# ethernet_1gbe_ext_magn.net
KiCad netlist of a schematic drawn in Altium Designer
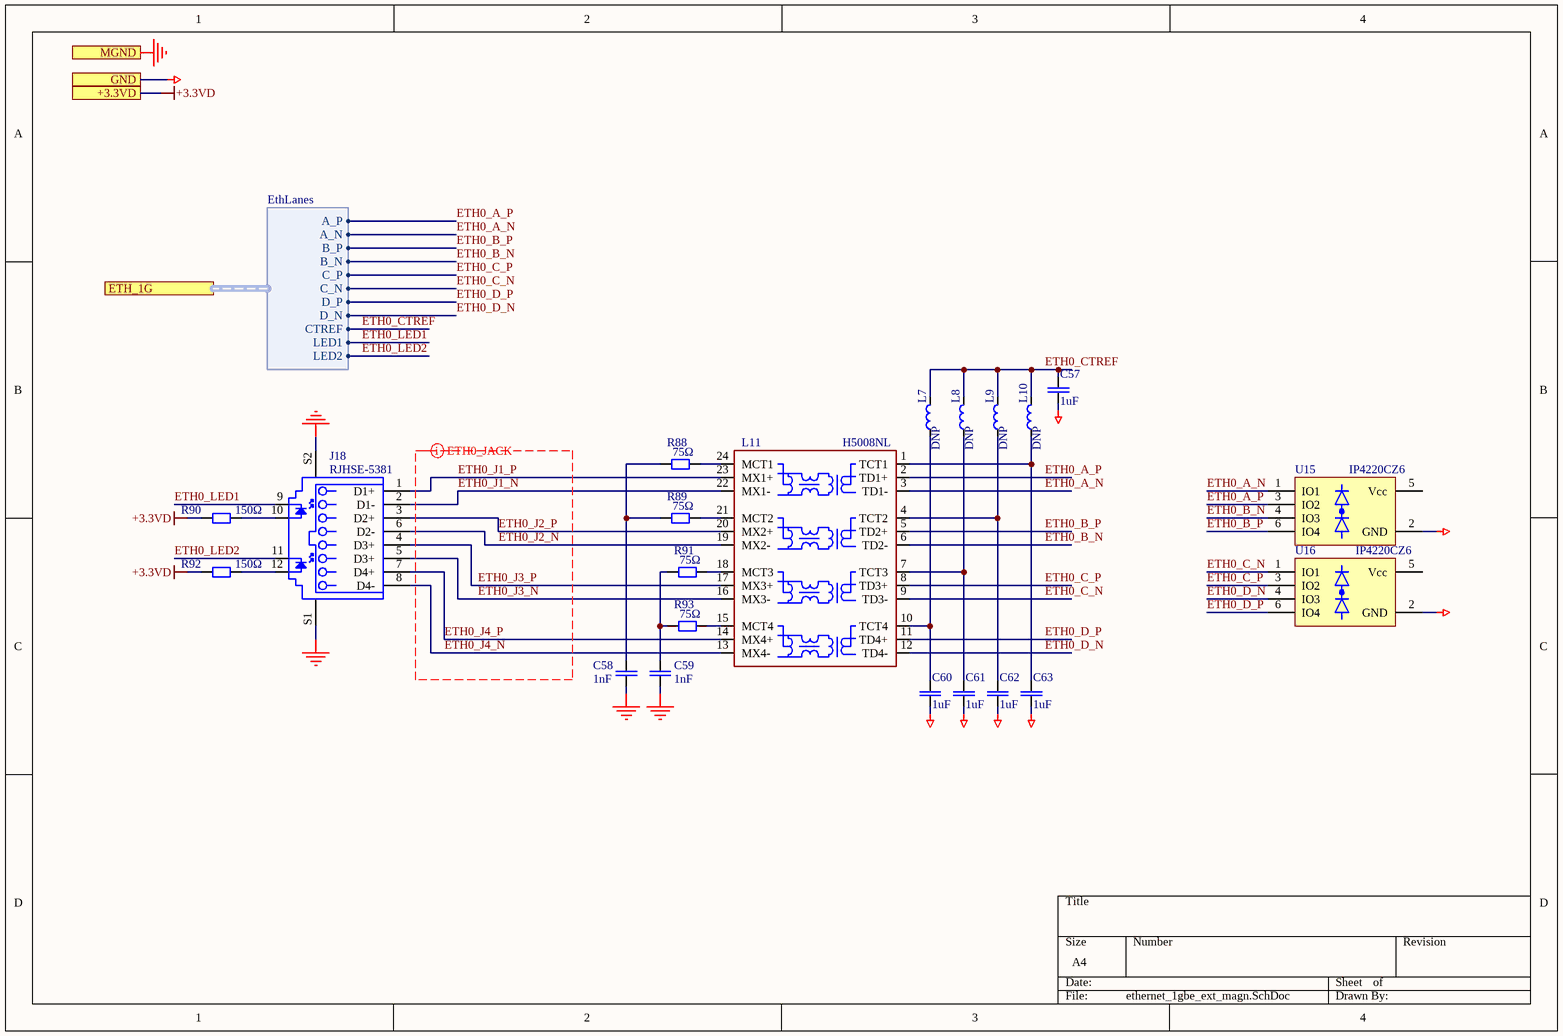
[diagram p0: ethernet_1gbe_ext_magn.SchDoc]

(export (version "E")
  (design (tool "Eeschema 10.0.6"))
  (components
    (comp (ref "C57")
      (value "1uF")
      (footprint "CAPC2012N")
      (description "Generic ceramic SMD capacitor")
      (fields (field (name "MAINTAINER") "Evgeniy Kotov"))
      (libsource (lib "[Capacitors] Capacitors SMD") (part "CAPC"))
    )
    (comp (ref "C58")
      (value "1nF")
      (footprint "CAPC3216N")
      (description "Generic ceramic SMD capacitor\r\n+' x '+Voltage Rating")
      (fields (field (name "Comment") "1nF; 2kV") (field (name "MAINTAINER") "Evgeniy Kotov"))
      (libsource (lib "[Capacitors] Capacitors SMD") (part "CAPC"))
    )
    (comp (ref "C59")
      (value "1nF")
      (footprint "CAPC3216N")
      (description "Generic ceramic SMD capacitor")
      (fields (field (name "Comment") "1nF; 2kV") (field (name "MAINTAINER") "Evgeniy Kotov"))
      (libsource (lib "[Capacitors] Capacitors SMD") (part "CAPC"))
    )
    (comp (ref "C60")
      (value "1uF")
      (footprint "CAPC2012N")
      (description "Generic ceramic SMD capacitor")
      (fields (field (name "MAINTAINER") "Evgeniy Kotov"))
      (libsource (lib "[Capacitors] Capacitors SMD") (part "CAPC"))
    )
    (comp (ref "C61")
      (value "1uF")
      (footprint "CAPC2012N")
      (description "Generic ceramic SMD capacitor")
      (fields (field (name "MAINTAINER") "Evgeniy Kotov"))
      (libsource (lib "[Capacitors] Capacitors SMD") (part "CAPC"))
    )
    (comp (ref "C62")
      (value "1uF")
      (footprint "CAPC2012N")
      (description "Generic ceramic SMD capacitor")
      (fields (field (name "MAINTAINER") "Evgeniy Kotov"))
      (libsource (lib "[Capacitors] Capacitors SMD") (part "CAPC"))
    )
    (comp (ref "C63")
      (value "1uF")
      (footprint "CAPC2012N")
      (description "Generic ceramic SMD capacitor")
      (fields (field (name "MAINTAINER") "Evgeniy Kotov"))
      (libsource (lib "[Capacitors] Capacitors SMD") (part "CAPC"))
    )
    (comp (ref "J18")
      (value "RJHSE-5381")
      (footprint "AMPH-RJHSE-5381_V")
      (fields (field (name "MANUFACTURER") "Amphenol"))
      (libsource (lib "[Connectors] Miscellaneous") (part "RJ45-RJHSE-5381"))
    )
    (comp (ref "L7")
      (value "DNP")
      (footprint "INDC2012N")
      (description "Ferrite Beads, 0805, 1 kOhm")
      (fields (field (name "TOLERANCE") "25%") (field (name "MAINTAINER") "Evgeniy Kotov"))
      (libsource (lib "[Inductors & Transformers] Inductors SMD") (part "BLM21RK102SN1D"))
    )
    (comp (ref "L8")
      (value "DNP")
      (footprint "INDC2012N")
      (description "Ferrite Beads, 0805, 1 kOhm")
      (fields (field (name "TOLERANCE") "25%") (field (name "MAINTAINER") "Evgeniy Kotov"))
      (libsource (lib "[Inductors & Transformers] Inductors SMD") (part "BLM21RK102SN1D"))
    )
    (comp (ref "L9")
      (value "DNP")
      (footprint "INDC2012N")
      (description "Ferrite Beads, 0805, 1 kOhm")
      (fields (field (name "TOLERANCE") "25%") (field (name "MAINTAINER") "Evgeniy Kotov"))
      (libsource (lib "[Inductors & Transformers] Inductors SMD") (part "BLM21RK102SN1D"))
    )
    (comp (ref "L10")
      (value "DNP")
      (footprint "INDC2012N")
      (description "Ferrite Beads, 0805, 1 kOhm")
      (fields (field (name "TOLERANCE") "25%") (field (name "MAINTAINER") "Evgeniy Kotov"))
      (libsource (lib "[Inductors & Transformers] Inductors SMD") (part "BLM21RK102SN1D"))
    )
    (comp (ref "L11")
      (value "H5008NL")
      (footprint "SMD_HX508")
      (description "LAN Transformer fog 1GbE, 12 coils, 4 pairs.")
      (fields (field (name "TOLERANCE") "2%") (field (name "MAINTAINER") "Evgeniy Kotov"))
      (libsource (lib "[Inductors & Transformers] Inductors SMD") (part "LAN_1G_TR_H5008NL"))
    )
    (comp (ref "R88")
      (value "75Ω")
      (footprint "RESC2012N")
      (description "Resistor, Generic, SMD")
      (fields (field (name "MAINTAINER") "Evgeniy Kotov"))
      (libsource (lib "[Resistors] Resistors SMD") (part "RESC"))
    )
    (comp (ref "R89")
      (value "75Ω")
      (footprint "RESC2012N")
      (description "Resistor, Generic, SMD")
      (fields (field (name "MAINTAINER") "Evgeniy Kotov"))
      (libsource (lib "[Resistors] Resistors SMD") (part "RESC"))
    )
    (comp (ref "R90")
      (value "150Ω")
      (footprint "RESC2012N")
      (description "Resistor, Generic, SMD")
      (fields (field (name "MAINTAINER") "Evgeniy Kotov"))
      (libsource (lib "[Resistors] Resistors SMD") (part "RESC"))
    )
    (comp (ref "R91")
      (value "75Ω")
      (footprint "RESC2012N")
      (description "Resistor, Generic, SMD")
      (fields (field (name "MAINTAINER") "Evgeniy Kotov"))
      (libsource (lib "[Resistors] Resistors SMD") (part "RESC"))
    )
    (comp (ref "R92")
      (value "150Ω")
      (footprint "RESC2012N")
      (description "Resistor, Generic, SMD")
      (fields (field (name "MAINTAINER") "Evgeniy Kotov"))
      (libsource (lib "[Resistors] Resistors SMD") (part "RESC"))
    )
    (comp (ref "R93")
      (value "75Ω")
      (footprint "RESC2012N")
      (description "Resistor, Generic, SMD")
      (fields (field (name "MAINTAINER") "Evgeniy Kotov"))
      (libsource (lib "[Resistors] Resistors SMD") (part "RESC"))
    )
    (comp (ref "U15")
      (value "IP4220CZ6")
      (footprint "SOT95P285X110-6N")
      (description "Transimpedance Amplifier; Selectable-Feedback Resistance")
      (fields (field (name "MAINTAINER") "Evgeniy Kotov"))
      (libsource (lib "[ICs And Semiconductors] Diodes") (part "IP4220CZ6"))
    )
    (comp (ref "U16")
      (value "IP4220CZ6")
      (footprint "SOT95P285X110-6N")
      (description "Transimpedance Amplifier; Selectable-Feedback Resistance")
      (fields (field (name "MAINTAINER") "Evgeniy Kotov"))
      (libsource (lib "[ICs And Semiconductors] Diodes") (part "IP4220CZ6"))
    )
  )
  (nets
    (net (code "2") (name "+3.3VD") (class "Default")
      (node (ref "R90") (pin "1") (pintype "passive"))
      (node (ref "R92") (pin "1") (pintype "passive"))
    )
    (net (code "3") (name "/ETH0_A_N") (class "Default")
      (node (ref "L11") (pin "3") (pinfunction "TD1-_3") (pintype "passive"))
      (node (ref "U15") (pin "1") (pinfunction "IO1_1") (pintype "passive"))
    )
    (net (code "4") (name "/ETH0_A_P") (class "Default")
      (node (ref "L11") (pin "2") (pinfunction "TD1+_2") (pintype "passive"))
      (node (ref "U15") (pin "3") (pinfunction "IO2_3") (pintype "passive"))
    )
    (net (code "5") (name "/ETH0_B_N") (class "Default")
      (node (ref "L11") (pin "6") (pinfunction "TD2-_6") (pintype "passive"))
      (node (ref "U15") (pin "4") (pinfunction "IO3_4") (pintype "passive"))
    )
    (net (code "6") (name "/ETH0_B_P") (class "Default")
      (node (ref "L11") (pin "5") (pinfunction "TD2+_5") (pintype "passive"))
      (node (ref "U15") (pin "6") (pinfunction "IO4_6") (pintype "passive"))
    )
    (net (code "7") (name "/ETH0_CTREF") (class "Default")
      (node (ref "C57") (pin "2") (pintype "passive"))
      (node (ref "L10") (pin "2") (pinfunction "2_2") (pintype "passive"))
      (node (ref "L7") (pin "2") (pinfunction "2_2") (pintype "passive"))
      (node (ref "L8") (pin "2") (pinfunction "2_2") (pintype "passive"))
      (node (ref "L9") (pin "2") (pinfunction "2_2") (pintype "passive"))
    )
    (net (code "8") (name "/ETH0_C_N") (class "Default")
      (node (ref "L11") (pin "9") (pinfunction "TD3-_9") (pintype "passive"))
      (node (ref "U16") (pin "1") (pinfunction "IO1_1") (pintype "passive"))
    )
    (net (code "9") (name "/ETH0_C_P") (class "Default")
      (node (ref "L11") (pin "8") (pinfunction "TD3+_8") (pintype "passive"))
      (node (ref "U16") (pin "3") (pinfunction "IO2_3") (pintype "passive"))
    )
    (net (code "10") (name "/ETH0_D_N") (class "Default")
      (node (ref "L11") (pin "12") (pinfunction "TD4-_12") (pintype "passive"))
      (node (ref "U16") (pin "4") (pinfunction "IO3_4") (pintype "passive"))
    )
    (net (code "11") (name "/ETH0_D_P") (class "Default")
      (node (ref "L11") (pin "11") (pinfunction "TD4+_11") (pintype "passive"))
      (node (ref "U16") (pin "6") (pinfunction "IO4_6") (pintype "passive"))
    )
    (net (code "12") (name "/ETH0_J1_N") (class "Default")
      (node (ref "J18") (pin "2") (pinfunction "D1-_2") (pintype "passive"))
      (node (ref "L11") (pin "22") (pinfunction "MX1-_22") (pintype "passive"))
    )
    (net (code "13") (name "/ETH0_J1_P") (class "Default")
      (node (ref "J18") (pin "1") (pinfunction "D1+_1") (pintype "passive"))
      (node (ref "L11") (pin "23") (pinfunction "MX1+_23") (pintype "passive"))
    )
    (net (code "14") (name "/ETH0_J2_N") (class "Default")
      (node (ref "J18") (pin "6") (pinfunction "D2-_6") (pintype "passive"))
      (node (ref "L11") (pin "19") (pinfunction "MX2-_19") (pintype "passive"))
    )
    (net (code "15") (name "/ETH0_J2_P") (class "Default")
      (node (ref "J18") (pin "3") (pinfunction "D2+_3") (pintype "passive"))
      (node (ref "L11") (pin "20") (pinfunction "MX2+_20") (pintype "passive"))
    )
    (net (code "16") (name "/ETH0_J3_N") (class "Default")
      (node (ref "J18") (pin "5") (pinfunction "D3+_5") (pintype "passive"))
      (node (ref "L11") (pin "16") (pinfunction "MX3-_16") (pintype "passive"))
    )
    (net (code "17") (name "/ETH0_J3_P") (class "Default")
      (node (ref "J18") (pin "4") (pinfunction "D3+_4") (pintype "passive"))
      (node (ref "L11") (pin "17") (pinfunction "MX3+_17") (pintype "passive"))
    )
    (net (code "18") (name "/ETH0_J4_N") (class "Default")
      (node (ref "J18") (pin "8") (pinfunction "D4-_8") (pintype "passive"))
      (node (ref "L11") (pin "13") (pinfunction "MX4-_13") (pintype "passive"))
    )
    (net (code "19") (name "/ETH0_J4_P") (class "Default")
      (node (ref "J18") (pin "7") (pinfunction "D4+_7") (pintype "passive"))
      (node (ref "L11") (pin "14") (pinfunction "MX4+_14") (pintype "passive"))
    )
    (net (code "20") (name "/ETH0_LED1") (class "Default")
      (node (ref "J18") (pin "9") (pinfunction "9_9") (pintype "passive"))
    )
    (net (code "21") (name "/ETH0_LED2") (class "Default")
      (node (ref "J18") (pin "11") (pinfunction "11_11") (pintype "passive"))
    )
    (net (code "23") (name "GND") (class "Default")
      (node (ref "C57") (pin "1") (pintype "passive"))
      (node (ref "C60") (pin "1") (pintype "passive"))
      (node (ref "C61") (pin "1") (pintype "passive"))
      (node (ref "C62") (pin "1") (pintype "passive"))
      (node (ref "C63") (pin "1") (pintype "passive"))
      (node (ref "U15") (pin "2") (pinfunction "GND_2") (pintype "passive"))
      (node (ref "U16") (pin "2") (pinfunction "GND_2") (pintype "passive"))
    )
    (net (code "24") (name "MGND") (class "Default")
      (node (ref "C58") (pin "1") (pintype "passive"))
      (node (ref "C59") (pin "1") (pintype "passive"))
      (node (ref "J18") (pin "S1") (pinfunction "S1_S1") (pintype "passive"))
      (node (ref "J18") (pin "S2") (pinfunction "S2_S2") (pintype "passive"))
    )
    (net (code "25") (name "Net-(C58-Pad2)") (class "Default")
      (node (ref "C58") (pin "2") (pintype "passive"))
      (node (ref "R88") (pin "1") (pintype "passive"))
      (node (ref "R89") (pin "1") (pintype "passive"))
    )
    (net (code "26") (name "Net-(C59-Pad2)") (class "Default")
      (node (ref "C59") (pin "2") (pintype "passive"))
      (node (ref "R91") (pin "1") (pintype "passive"))
      (node (ref "R93") (pin "1") (pintype "passive"))
    )
    (net (code "27") (name "Net-(J18-Pad10)") (class "Default")
      (node (ref "J18") (pin "10") (pinfunction "10_10") (pintype "passive"))
      (node (ref "R90") (pin "2") (pintype "passive"))
    )
    (net (code "28") (name "Net-(J18-Pad12)") (class "Default")
      (node (ref "J18") (pin "12") (pinfunction "12_12") (pintype "passive"))
      (node (ref "R92") (pin "2") (pintype "passive"))
    )
    (net (code "29") (name "Net-(L11-MCT1)") (class "Default")
      (node (ref "L11") (pin "24") (pinfunction "MCT1_24") (pintype "passive"))
      (node (ref "R88") (pin "2") (pintype "passive"))
    )
    (net (code "30") (name "Net-(L11-MCT2)") (class "Default")
      (node (ref "L11") (pin "21") (pinfunction "MCT2_21") (pintype "passive"))
      (node (ref "R89") (pin "2") (pintype "passive"))
    )
    (net (code "31") (name "Net-(L11-MCT3)") (class "Default")
      (node (ref "L11") (pin "18") (pinfunction "MCT3_18") (pintype "passive"))
      (node (ref "R91") (pin "2") (pintype "passive"))
    )
    (net (code "32") (name "Net-(L11-MCT4)") (class "Default")
      (node (ref "L11") (pin "15") (pinfunction "MCT4_15") (pintype "passive"))
      (node (ref "R93") (pin "2") (pintype "passive"))
    )
    (net (code "33") (name "Net-(L11-TCT1)") (class "Default")
      (node (ref "C63") (pin "2") (pintype "passive"))
      (node (ref "L10") (pin "1") (pinfunction "1_1") (pintype "passive"))
      (node (ref "L11") (pin "1") (pinfunction "TCT1_1") (pintype "passive"))
    )
    (net (code "34") (name "Net-(L11-TCT2)") (class "Default")
      (node (ref "C62") (pin "2") (pintype "passive"))
      (node (ref "L11") (pin "4") (pinfunction "TCT2_4") (pintype "passive"))
      (node (ref "L9") (pin "1") (pinfunction "1_1") (pintype "passive"))
    )
    (net (code "35") (name "Net-(L11-TCT3)") (class "Default")
      (node (ref "C61") (pin "2") (pintype "passive"))
      (node (ref "L11") (pin "7") (pinfunction "TCT3_7") (pintype "passive"))
      (node (ref "L8") (pin "1") (pinfunction "1_1") (pintype "passive"))
    )
    (net (code "36") (name "Net-(L11-TCT4)") (class "Default")
      (node (ref "C60") (pin "2") (pintype "passive"))
      (node (ref "L11") (pin "10") (pinfunction "TCT4_10") (pintype "passive"))
      (node (ref "L7") (pin "1") (pinfunction "1_1") (pintype "passive"))
    )
    (net (code "37") (name "unconnected-(U15-Vcc-Pad5)") (class "Default")
      (node (ref "U15") (pin "5") (pinfunction "Vcc_5") (pintype "passive"))
    )
    (net (code "38") (name "unconnected-(U16-Vcc-Pad5)") (class "Default")
      (node (ref "U16") (pin "5") (pinfunction "Vcc_5") (pintype "passive"))
    )
  )
)
